# interface.net
KiCad netlist of a schematic drawn in EAGLE
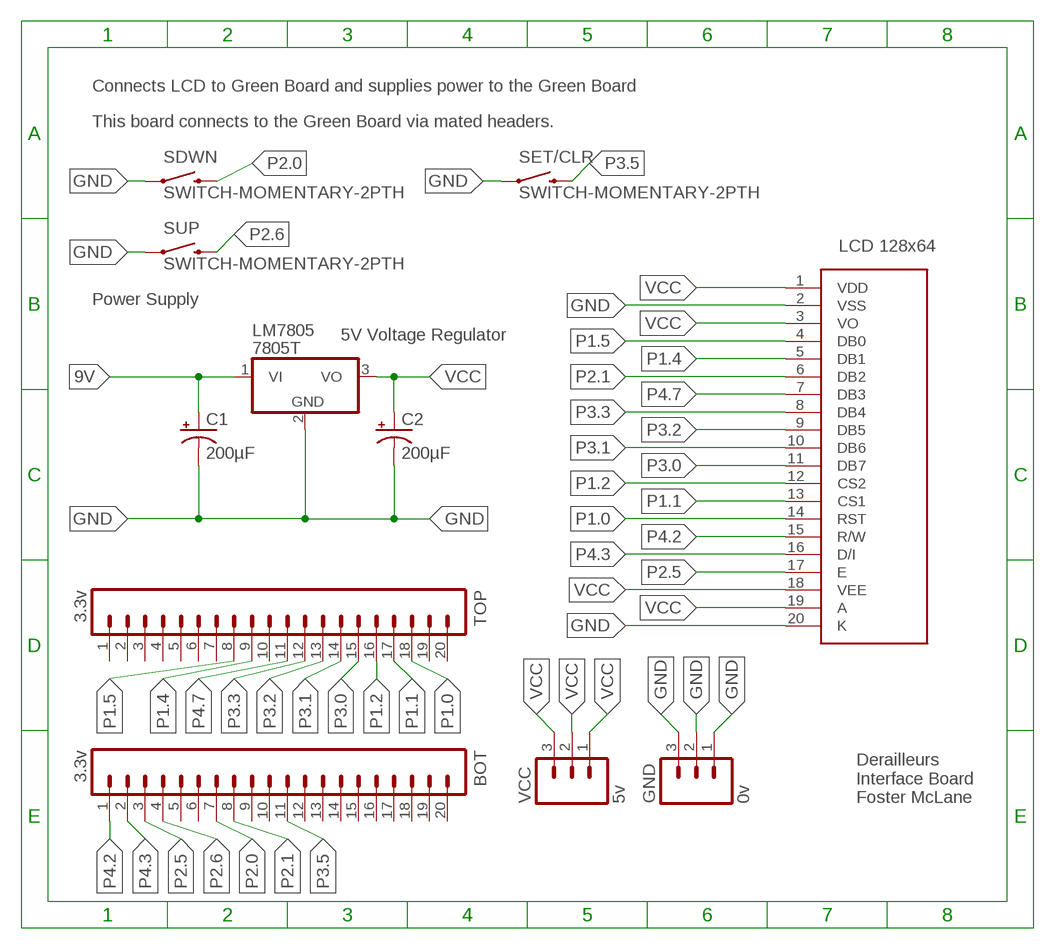
[diagram p0: schematic, sheet 1]

(export (version "E")
  (design (tool "Eeschema 10.0.6"))
  (components
    (comp (ref "BOT")
      (value "3.3v")
      (footprint "eagle-import:1X20")
      (libsource (lib "eagle-import") (part "M20"))
    )
    (comp (ref "C1")
      (value "200µF")
      (footprint "eagle-import:CPOL-RADIAL-100UF-25V")
      (libsource (lib "eagle-import") (part "CAP_POLPTH1"))
    )
    (comp (ref "C2")
      (value "200µF")
      (footprint "eagle-import:CPOL-RADIAL-100UF-25V")
      (libsource (lib "eagle-import") (part "CAP_POLPTH1"))
    )
    (comp (ref "GND")
      (value "0v")
      (footprint "eagle-import:1X03")
      (libsource (lib "eagle-import") (part "M03PTH"))
    )
    (comp (ref "LM7805")
      (value "7805T")
      (footprint "eagle-import:TO220H")
      (libsource (lib "eagle-import") (part "78T05"))
    )
    (comp (ref "SDWN")
      (value "SWITCH-MOMENTARY-2PTH")
      (footprint "eagle-import:TACTILE-PTH")
      (libsource (lib "eagle-import") (part "SWITCH-MOMENTARY-2PTH"))
    )
    (comp (ref "SET/CLR")
      (value "SWITCH-MOMENTARY-2PTH")
      (footprint "eagle-import:TACTILE-PTH")
      (libsource (lib "eagle-import") (part "SWITCH-MOMENTARY-2PTH"))
    )
    (comp (ref "SUP")
      (value "SWITCH-MOMENTARY-2PTH")
      (footprint "eagle-import:TACTILE-PTH")
      (libsource (lib "eagle-import") (part "SWITCH-MOMENTARY-2PTH"))
    )
    (comp (ref "TOP")
      (value "3.3v")
      (footprint "eagle-import:1X20")
      (libsource (lib "eagle-import") (part "M20"))
    )
    (comp (ref "U$1")
      (value "LCD-G12864FULL")
      (footprint "eagle-import:LCD-G12864")
      (libsource (lib "eagle-import") (part "LCD-G12864FULL"))
    )
    (comp (ref "VCC")
      (value "5v")
      (footprint "eagle-import:1X03")
      (libsource (lib "eagle-import") (part "M03PTH"))
    )
  )
  (nets
    (net (code "1") (name "9V") (class "Default")
      (node (ref "C1") (pin "1") (pinfunction "+_1") (pintype "passive"))
      (node (ref "LM7805") (pin "1") (pinfunction "VI_1") (pintype "input"))
    )
    (net (code "2") (name "GND") (class "Default")
      (node (ref "C1") (pin "2") (pinfunction "-_2") (pintype "passive"))
      (node (ref "C2") (pin "2") (pinfunction "-_2") (pintype "passive"))
      (node (ref "GND") (pin "1") (pinfunction "1_1") (pintype "passive"))
      (node (ref "GND") (pin "2") (pinfunction "2_2") (pintype "passive"))
      (node (ref "GND") (pin "3") (pinfunction "3_3") (pintype "passive"))
      (node (ref "LM7805") (pin "2") (pinfunction "GND_2") (pintype "passive"))
      (node (ref "SDWN") (pin "1") (pinfunction "1_1") (pintype "passive"))
      (node (ref "SET/CLR") (pin "1") (pinfunction "1_1") (pintype "passive"))
      (node (ref "SUP") (pin "1") (pinfunction "1_1") (pintype "passive"))
      (node (ref "U$1") (pin "2") (pinfunction "VSS_2") (pintype "power_in"))
      (node (ref "U$1") (pin "20") (pinfunction "K_20") (pintype "power_in"))
    )
    (net (code "3") (name "P1.0") (class "Default")
      (node (ref "TOP") (pin "18") (pinfunction "18_18") (pintype "passive"))
      (node (ref "U$1") (pin "14") (pinfunction "RST_14") (pintype "input"))
    )
    (net (code "4") (name "P1.1") (class "Default")
      (node (ref "TOP") (pin "17") (pinfunction "17_17") (pintype "passive"))
      (node (ref "U$1") (pin "13") (pinfunction "CS1_13") (pintype "input"))
    )
    (net (code "5") (name "P1.2") (class "Default")
      (node (ref "TOP") (pin "16") (pinfunction "16_16") (pintype "passive"))
      (node (ref "U$1") (pin "12") (pinfunction "CS2_12") (pintype "input"))
    )
    (net (code "6") (name "P1.4") (class "Default")
      (node (ref "TOP") (pin "9") (pinfunction "9_9") (pintype "passive"))
      (node (ref "U$1") (pin "5") (pinfunction "DB1_5") (pintype "bidirectional"))
    )
    (net (code "7") (name "P1.5") (class "Default")
      (node (ref "TOP") (pin "8") (pinfunction "8_8") (pintype "passive"))
      (node (ref "U$1") (pin "4") (pinfunction "DB0_4") (pintype "bidirectional"))
    )
    (net (code "8") (name "P2.0") (class "Default")
      (node (ref "BOT") (pin "7") (pinfunction "7_7") (pintype "passive"))
      (node (ref "SDWN") (pin "3") (pinfunction "2_3") (pintype "passive"))
    )
    (net (code "9") (name "P2.1") (class "Default")
      (node (ref "BOT") (pin "8") (pinfunction "8_8") (pintype "passive"))
      (node (ref "U$1") (pin "6") (pinfunction "DB2_6") (pintype "bidirectional"))
    )
    (net (code "10") (name "P2.5") (class "Default")
      (node (ref "BOT") (pin "3") (pinfunction "3_3") (pintype "passive"))
      (node (ref "U$1") (pin "17") (pinfunction "E_17") (pintype "input"))
    )
    (net (code "11") (name "P2.6") (class "Default")
      (node (ref "BOT") (pin "4") (pinfunction "4_4") (pintype "passive"))
      (node (ref "SUP") (pin "3") (pinfunction "2_3") (pintype "passive"))
    )
    (net (code "12") (name "P3.0") (class "Default")
      (node (ref "TOP") (pin "15") (pinfunction "15_15") (pintype "passive"))
      (node (ref "U$1") (pin "11") (pinfunction "DB7_11") (pintype "bidirectional"))
    )
    (net (code "13") (name "P3.1") (class "Default")
      (node (ref "TOP") (pin "14") (pinfunction "14_14") (pintype "passive"))
      (node (ref "U$1") (pin "10") (pinfunction "DB6_10") (pintype "bidirectional"))
    )
    (net (code "14") (name "P3.2") (class "Default")
      (node (ref "TOP") (pin "13") (pinfunction "13_13") (pintype "passive"))
      (node (ref "U$1") (pin "9") (pinfunction "DB5_9") (pintype "bidirectional"))
    )
    (net (code "15") (name "P3.3") (class "Default")
      (node (ref "TOP") (pin "12") (pinfunction "12_12") (pintype "passive"))
      (node (ref "U$1") (pin "8") (pinfunction "DB4_8") (pintype "bidirectional"))
    )
    (net (code "16") (name "P3.5") (class "Default")
      (node (ref "BOT") (pin "11") (pinfunction "11_11") (pintype "passive"))
      (node (ref "SET/CLR") (pin "3") (pinfunction "2_3") (pintype "passive"))
    )
    (net (code "17") (name "P4.2") (class "Default")
      (node (ref "BOT") (pin "1") (pinfunction "1_1") (pintype "passive"))
      (node (ref "U$1") (pin "15") (pinfunction "R/W_15") (pintype "input"))
    )
    (net (code "18") (name "P4.3") (class "Default")
      (node (ref "BOT") (pin "2") (pinfunction "2_2") (pintype "passive"))
      (node (ref "U$1") (pin "16") (pinfunction "D/I_16") (pintype "input"))
    )
    (net (code "19") (name "P4.7") (class "Default")
      (node (ref "TOP") (pin "11") (pinfunction "11_11") (pintype "passive"))
      (node (ref "U$1") (pin "7") (pinfunction "DB3_7") (pintype "bidirectional"))
    )
    (net (code "20") (name "VCC") (class "Default")
      (node (ref "C2") (pin "1") (pinfunction "+_1") (pintype "passive"))
      (node (ref "LM7805") (pin "3") (pinfunction "VO_3") (pintype "passive"))
      (node (ref "U$1") (pin "1") (pinfunction "VDD_1") (pintype "power_in"))
      (node (ref "U$1") (pin "18") (pinfunction "VEE_18") (pintype "bidirectional"))
      (node (ref "U$1") (pin "19") (pinfunction "A_19") (pintype "power_in"))
      (node (ref "U$1") (pin "3") (pinfunction "VO_3") (pintype "bidirectional"))
      (node (ref "VCC") (pin "1") (pinfunction "1_1") (pintype "passive"))
      (node (ref "VCC") (pin "2") (pinfunction "2_2") (pintype "passive"))
      (node (ref "VCC") (pin "3") (pinfunction "3_3") (pintype "passive"))
    )
    (net (code "21") (name "unconnected-(BOT-Pad5)") (class "Default")
      (node (ref "BOT") (pin "5") (pinfunction "5_5") (pintype "passive"))
    )
    (net (code "22") (name "unconnected-(BOT-Pad6)") (class "Default")
      (node (ref "BOT") (pin "6") (pinfunction "6_6") (pintype "passive"))
    )
    (net (code "23") (name "unconnected-(BOT-Pad9)") (class "Default")
      (node (ref "BOT") (pin "9") (pinfunction "9_9") (pintype "passive"))
    )
    (net (code "24") (name "unconnected-(BOT-Pad10)") (class "Default")
      (node (ref "BOT") (pin "10") (pinfunction "10_10") (pintype "passive"))
    )
    (net (code "25") (name "unconnected-(BOT-Pad12)") (class "Default")
      (node (ref "BOT") (pin "12") (pinfunction "12_12") (pintype "passive"))
    )
    (net (code "26") (name "unconnected-(BOT-Pad13)") (class "Default")
      (node (ref "BOT") (pin "13") (pinfunction "13_13") (pintype "passive"))
    )
    (net (code "27") (name "unconnected-(BOT-Pad14)") (class "Default")
      (node (ref "BOT") (pin "14") (pinfunction "14_14") (pintype "passive"))
    )
    (net (code "28") (name "unconnected-(BOT-Pad15)") (class "Default")
      (node (ref "BOT") (pin "15") (pinfunction "15_15") (pintype "passive"))
    )
    (net (code "29") (name "unconnected-(BOT-Pad16)") (class "Default")
      (node (ref "BOT") (pin "16") (pinfunction "16_16") (pintype "passive"))
    )
    (net (code "30") (name "unconnected-(BOT-Pad17)") (class "Default")
      (node (ref "BOT") (pin "17") (pinfunction "17_17") (pintype "passive"))
    )
    (net (code "31") (name "unconnected-(BOT-Pad18)") (class "Default")
      (node (ref "BOT") (pin "18") (pinfunction "18_18") (pintype "passive"))
    )
    (net (code "32") (name "unconnected-(BOT-Pad19)") (class "Default")
      (node (ref "BOT") (pin "19") (pinfunction "19_19") (pintype "passive"))
    )
    (net (code "33") (name "unconnected-(BOT-Pad20)") (class "Default")
      (node (ref "BOT") (pin "20") (pinfunction "20_20") (pintype "passive"))
    )
    (net (code "34") (name "unconnected-(TOP-Pad1)") (class "Default")
      (node (ref "TOP") (pin "1") (pinfunction "1_1") (pintype "passive"))
    )
    (net (code "35") (name "unconnected-(TOP-Pad2)") (class "Default")
      (node (ref "TOP") (pin "2") (pinfunction "2_2") (pintype "passive"))
    )
    (net (code "36") (name "unconnected-(TOP-Pad3)") (class "Default")
      (node (ref "TOP") (pin "3") (pinfunction "3_3") (pintype "passive"))
    )
    (net (code "37") (name "unconnected-(TOP-Pad4)") (class "Default")
      (node (ref "TOP") (pin "4") (pinfunction "4_4") (pintype "passive"))
    )
    (net (code "38") (name "unconnected-(TOP-Pad5)") (class "Default")
      (node (ref "TOP") (pin "5") (pinfunction "5_5") (pintype "passive"))
    )
    (net (code "39") (name "unconnected-(TOP-Pad6)") (class "Default")
      (node (ref "TOP") (pin "6") (pinfunction "6_6") (pintype "passive"))
    )
    (net (code "40") (name "unconnected-(TOP-Pad7)") (class "Default")
      (node (ref "TOP") (pin "7") (pinfunction "7_7") (pintype "passive"))
    )
    (net (code "41") (name "unconnected-(TOP-Pad10)") (class "Default")
      (node (ref "TOP") (pin "10") (pinfunction "10_10") (pintype "passive"))
    )
    (net (code "42") (name "unconnected-(TOP-Pad19)") (class "Default")
      (node (ref "TOP") (pin "19") (pinfunction "19_19") (pintype "passive"))
    )
    (net (code "43") (name "unconnected-(TOP-Pad20)") (class "Default")
      (node (ref "TOP") (pin "20") (pinfunction "20_20") (pintype "passive"))
    )
  )
)
